# Analog.net
KiCad netlist of a schematic drawn in Altium Designer
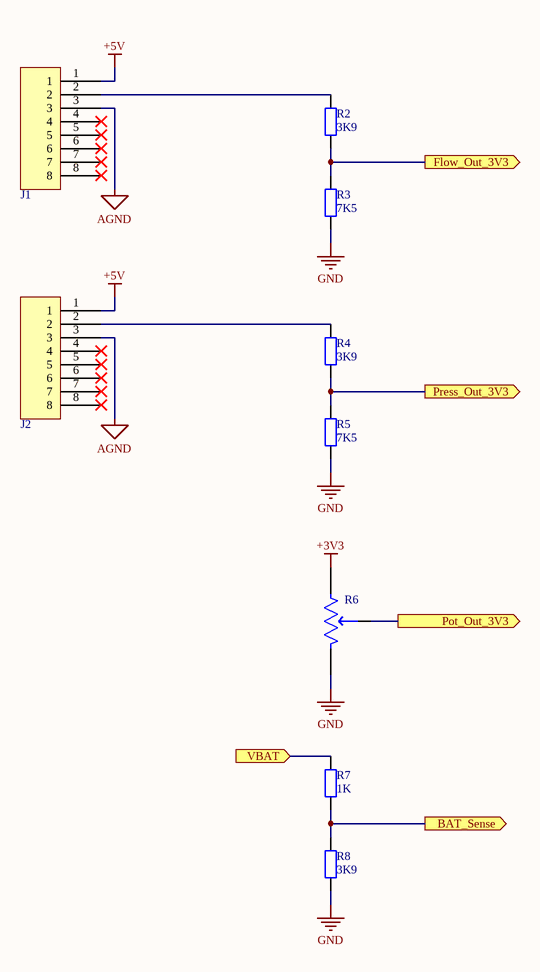
[diagram p0: Analog.SchDoc]

(export (version "E")
  (design (tool "Eeschema 10.0.6"))
  (components
    (comp (ref "J1")
      (value "MTJ-885X1")
      (footprint "MTJ-885X1")
      (fields (field (name "MANUFACTURER") "MODULAR JACK RJ45 8P8C"))
      (libsource (lib "Database_library") (part "MTJ-885X1"))
    )
    (comp (ref "J2")
      (value "MTJ-885X1")
      (footprint "MTJ-885X1")
      (fields (field (name "MANUFACTURER") "MODULAR JACK RJ45 8P8C"))
      (libsource (lib "Database_library") (part "MTJ-885X1"))
    )
    (comp (ref "R2")
      (value "3K9")
      (footprint "RES 0603/1608")
      (description "RES SMD 3.9K OHM 1% 1/10W 0603")
      (fields (field (name "PART NUMBER") "RC0603FR-073K9L") (field (name "TOLERANCE") "±1%"))
      (libsource (lib "electric_racing_lib") (part "Resistor"))
    )
    (comp (ref "R3")
      (value "7K5")
      (footprint "RES 0603/1608")
      (description "RES SMD 7.5K OHM 1% 1/10W 0603")
      (fields (field (name "PART NUMBER") "RC0603FR-077K5L") (field (name "TOLERANCE") "±1%"))
      (libsource (lib "electric_racing_lib") (part "Resistor"))
    )
    (comp (ref "R4")
      (value "3K9")
      (footprint "RES 0603/1608")
      (description "RES SMD 3.9K OHM 1% 1/10W 0603")
      (fields (field (name "PART NUMBER") "RC0603FR-073K9L") (field (name "TOLERANCE") "±1%"))
      (libsource (lib "electric_racing_lib") (part "Resistor"))
    )
    (comp (ref "R5")
      (value "7K5")
      (footprint "RES 0603/1608")
      (description "RES SMD 7.5K OHM 1% 1/10W 0603")
      (fields (field (name "PART NUMBER") "RC0603FR-077K5L") (field (name "TOLERANCE") "±1%"))
      (libsource (lib "electric_racing_lib") (part "Resistor"))
    )
    (comp (ref "R6")
      (value "PDB12-H4301-103BF")
      (footprint "PDB12-H4301-103BF")
      (description "Variable Resistor Symbol")
      (fields (field (name "MANUFACTURER") "Bourns Inc."))
      (libsource (lib "Database_library") (part "Pot"))
    )
    (comp (ref "R7")
      (value "1K")
      (footprint "RES 0603/1608")
      (description "RES SMD 1K OHM 1% 1/10W 0603")
      (fields (field (name "PART NUMBER") "RC0603FR-071KL") (field (name "TOLERANCE") "±1%"))
      (libsource (lib "electric_racing_lib") (part "Resistor"))
    )
    (comp (ref "R8")
      (value "3K9")
      (footprint "RES 0603/1608")
      (description "RES SMD 3.9K OHM 1% 1/10W 0603")
      (fields (field (name "PART NUMBER") "RC0603FR-073K9L") (field (name "TOLERANCE") "±1%"))
      (libsource (lib "electric_racing_lib") (part "Resistor"))
    )
  )
  (nets
    (net (code "1") (name "+3V3") (class "Default")
      (node (ref "R6") (pin "1") (pinfunction "1_1") (pintype "passive"))
    )
    (net (code "2") (name "+5V") (class "Default")
      (node (ref "J1") (pin "1") (pinfunction "1_1") (pintype "passive"))
      (node (ref "J2") (pin "1") (pinfunction "1_1") (pintype "passive"))
    )
    (net (code "3") (name "/BAT_Sense") (class "Default")
      (node (ref "R7") (pin "1") (pinfunction "1_1") (pintype "passive"))
      (node (ref "R8") (pin "2") (pinfunction "2_2") (pintype "passive"))
    )
    (net (code "4") (name "/Flow_Out_3V3") (class "Default")
      (node (ref "R2") (pin "1") (pinfunction "1_1") (pintype "passive"))
      (node (ref "R3") (pin "2") (pinfunction "2_2") (pintype "passive"))
    )
    (net (code "5") (name "/Pot_Out_3V3") (class "Default")
      (node (ref "R6") (pin "2") (pinfunction "2_2") (pintype "passive"))
    )
    (net (code "6") (name "/Press_Out_3V3") (class "Default")
      (node (ref "R4") (pin "1") (pinfunction "1_1") (pintype "passive"))
      (node (ref "R5") (pin "2") (pinfunction "2_2") (pintype "passive"))
    )
    (net (code "7") (name "/VBAT") (class "Default")
      (node (ref "R7") (pin "2") (pinfunction "2_2") (pintype "passive"))
    )
    (net (code "8") (name "AGND") (class "Default")
      (node (ref "J1") (pin "3") (pinfunction "3_3") (pintype "passive"))
      (node (ref "J2") (pin "3") (pinfunction "3_3") (pintype "passive"))
    )
    (net (code "9") (name "GND") (class "Default")
      (node (ref "R3") (pin "1") (pinfunction "1_1") (pintype "passive"))
      (node (ref "R5") (pin "1") (pinfunction "1_1") (pintype "passive"))
      (node (ref "R6") (pin "3") (pinfunction "3_3") (pintype "passive"))
      (node (ref "R8") (pin "1") (pinfunction "1_1") (pintype "passive"))
    )
    (net (code "10") (name "Net-(J1-Pad2)") (class "Default")
      (node (ref "J1") (pin "2") (pinfunction "2_2") (pintype "passive"))
      (node (ref "R2") (pin "2") (pinfunction "2_2") (pintype "passive"))
    )
    (net (code "11") (name "Net-(J2-Pad2)") (class "Default")
      (node (ref "J2") (pin "2") (pinfunction "2_2") (pintype "passive"))
      (node (ref "R4") (pin "2") (pinfunction "2_2") (pintype "passive"))
    )
    (net (code "12") (name "unconnected-(J1-Pad4)") (class "Default")
      (node (ref "J1") (pin "4") (pinfunction "4_4") (pintype "passive+no_connect"))
    )
    (net (code "13") (name "unconnected-(J1-Pad5)") (class "Default")
      (node (ref "J1") (pin "5") (pinfunction "5_5") (pintype "passive+no_connect"))
    )
    (net (code "14") (name "unconnected-(J1-Pad6)") (class "Default")
      (node (ref "J1") (pin "6") (pinfunction "6_6") (pintype "passive+no_connect"))
    )
    (net (code "15") (name "unconnected-(J1-Pad7)") (class "Default")
      (node (ref "J1") (pin "7") (pinfunction "7_7") (pintype "passive+no_connect"))
    )
    (net (code "16") (name "unconnected-(J1-Pad8)") (class "Default")
      (node (ref "J1") (pin "8") (pinfunction "8_8") (pintype "passive+no_connect"))
    )
    (net (code "17") (name "unconnected-(J2-Pad4)") (class "Default")
      (node (ref "J2") (pin "4") (pinfunction "4_4") (pintype "passive+no_connect"))
    )
    (net (code "18") (name "unconnected-(J2-Pad5)") (class "Default")
      (node (ref "J2") (pin "5") (pinfunction "5_5") (pintype "passive+no_connect"))
    )
    (net (code "19") (name "unconnected-(J2-Pad6)") (class "Default")
      (node (ref "J2") (pin "6") (pinfunction "6_6") (pintype "passive+no_connect"))
    )
    (net (code "20") (name "unconnected-(J2-Pad7)") (class "Default")
      (node (ref "J2") (pin "7") (pinfunction "7_7") (pintype "passive+no_connect"))
    )
    (net (code "21") (name "unconnected-(J2-Pad8)") (class "Default")
      (node (ref "J2") (pin "8") (pinfunction "8_8") (pintype "passive+no_connect"))
    )
  )
)
